# HOL-Nova.net
KiCad netlist of a schematic drawn in Altium Designer
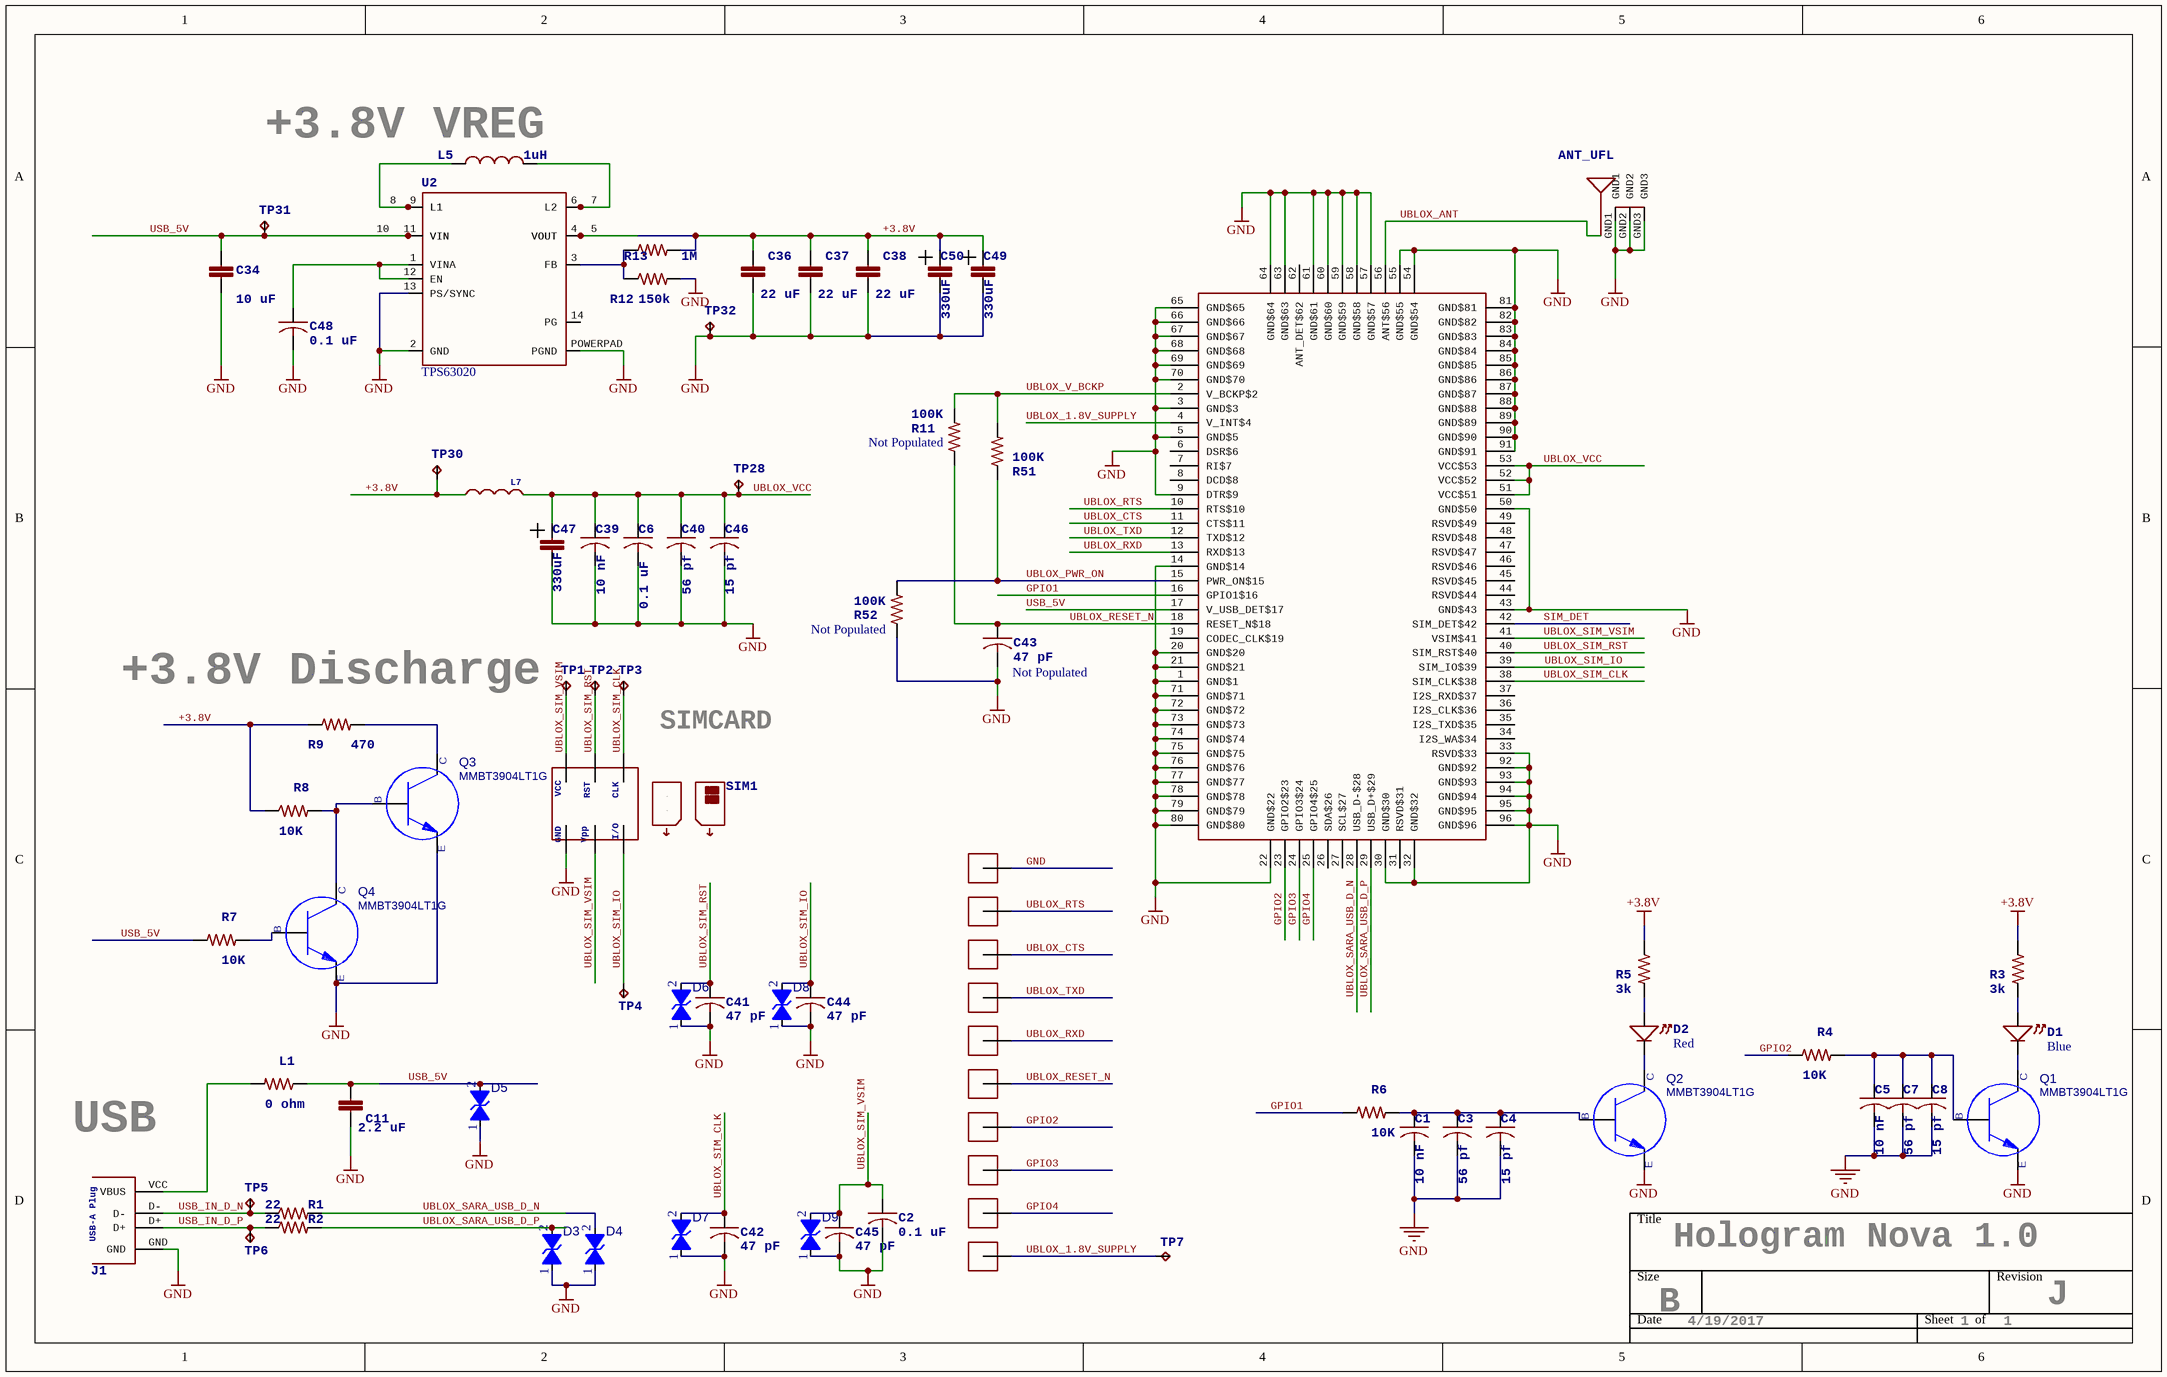
[diagram p0: HOL-Nova.SchDoc]

(export (version "E")
  (design (tool "Eeschema 10.0.6"))
  (components
    (comp (ref "ANT_UFL")
      (value "ANT-A-1JB")
      (footprint "UFL")
      (fields (field (name "MFG") "Amphenol") (field (name "MPN") "A-1JB"))
      (libsource (lib "KON-SU260") (part "ANT-A-1JB"))
    )
    (comp (ref "C1")
      (value "10 nF")
      (footprint "KON-SU260:CAP0402")
      (description "CAPACITOR, American symbol")
      (fields (field (name "MFG") "MURATA") (field (name "MPN") "GRM155R71C103KA01D"))
      (libsource (lib "KON-SU260") (part "CAP10nF_0402"))
    )
    (comp (ref "C2")
      (value "0.1 uF")
      (footprint "KON-SU260:CAP0402")
      (description "CAPACITOR, American symbol")
      (fields (field (name "MFG") "MURATA") (field (name "MPN") "GRM155R61C104KA88D"))
      (libsource (lib "KON-SU260") (part "CAP0.1uF_0402"))
    )
    (comp (ref "C3")
      (value "56 pf")
      (footprint "KON-SU260:CAP0402")
      (description "CAPACITOR, American symbol")
      (fields (field (name "MFG") "KEMET") (field (name "MPN") "C0402C560J5GACTU"))
      (libsource (lib "KON-SU260") (part "CAP56pF_0402"))
    )
    (comp (ref "C4")
      (value "15 pf")
      (footprint "KON-SU260:CAP0402")
      (description "CAPACITOR, American symbol")
      (fields (field (name "MFG") "AVX/ELCO") (field (name "MPN") "04025A150JAT2A"))
      (libsource (lib "KON-SU260") (part "CAP15pF_0402"))
    )
    (comp (ref "C5")
      (value "10 nF")
      (footprint "KON-SU260:CAP0402")
      (description "CAPACITOR, American symbol")
      (fields (field (name "MFG") "MURATA") (field (name "MPN") "GRM155R71C103KA01D"))
      (libsource (lib "KON-SU260") (part "CAP10nF_0402"))
    )
    (comp (ref "C6")
      (value "0.1 uF")
      (footprint "KON-SU260:CAP0402")
      (description "CAPACITOR, American symbol")
      (fields (field (name "MFG") "MURATA") (field (name "MPN") "GRM155R61C104KA88D"))
      (libsource (lib "KON-SU260") (part "CAP0.1uF_0402"))
    )
    (comp (ref "C7")
      (value "56 pf")
      (footprint "KON-SU260:CAP0402")
      (description "CAPACITOR, American symbol")
      (fields (field (name "MFG") "KEMET") (field (name "MPN") "C0402C560J5GACTU"))
      (libsource (lib "KON-SU260") (part "CAP56pF_0402"))
    )
    (comp (ref "C8")
      (value "15 pf")
      (footprint "KON-SU260:CAP0402")
      (description "CAPACITOR, American symbol")
      (fields (field (name "MFG") "AVX/ELCO") (field (name "MPN") "04025A150JAT2A"))
      (libsource (lib "KON-SU260") (part "CAP15pF_0402"))
    )
    (comp (ref "C11")
      (value "2.2 uF")
      (footprint "KON-SU260:CAP0603")
      (description "Ceramic Capacitor SMD")
      (fields (field (name "MPN") "CL10A225MQ8NNNC") (field (name "MFG") "SAMSUNG"))
      (libsource (lib "KON-SU260") (part "CAP2.2uF_0603"))
    )
    (comp (ref "C34")
      (value "10 uF")
      (footprint "KON-SU260:CAP0603")
      (description "Ceramic Capacitor SMD")
      (fields (field (name "MPN") "GRM188R60J106ME84D") (field (name "MFG") "Murata"))
      (libsource (lib "KON-SU260") (part "CAP10uF_0603"))
    )
    (comp (ref "C36")
      (value "22 uF")
      (footprint "KON-SU260:CAP0603")
      (description "Ceramic Capacitor SMD")
      (fields (field (name "MPN") "GRM188R60J226MEA0D") (field (name "MFG") "MURATA"))
      (libsource (lib "KON-SU260") (part "CAP22uF_0603"))
    )
    (comp (ref "C37")
      (value "22 uF")
      (footprint "KON-SU260:CAP0603")
      (description "Ceramic Capacitor SMD")
      (fields (field (name "MPN") "GRM188R60J226MEA0D") (field (name "MFG") "MURATA"))
      (libsource (lib "KON-SU260") (part "CAP22uF_0603"))
    )
    (comp (ref "C38")
      (value "22 uF")
      (footprint "KON-SU260:CAP0603")
      (description "Ceramic Capacitor SMD")
      (fields (field (name "MPN") "GRM188R60J226MEA0D") (field (name "MFG") "MURATA"))
      (libsource (lib "KON-SU260") (part "CAP22uF_0603"))
    )
    (comp (ref "C39")
      (value "10 nF")
      (footprint "KON-SU260:CAP0402")
      (description "CAPACITOR, American symbol")
      (fields (field (name "MFG") "MURATA") (field (name "MPN") "GRM155R71C103KA01D"))
      (libsource (lib "KON-SU260") (part "CAP10nF_0402"))
    )
    (comp (ref "C40")
      (value "56 pf")
      (footprint "KON-SU260:CAP0402")
      (description "CAPACITOR, American symbol")
      (fields (field (name "MFG") "KEMET") (field (name "MPN") "C0402C560J5GACTU"))
      (libsource (lib "KON-SU260") (part "CAP56pF_0402"))
    )
    (comp (ref "C41")
      (value "47 pF")
      (footprint "KON-SU260:CAP0402")
      (description "CAPACITOR, American symbol")
      (fields (field (name "MFG") "AVX") (field (name "MPN") "04025A470JAT2A"))
      (libsource (lib "KON-SU260") (part "CAP47pf_0402"))
    )
    (comp (ref "C42")
      (value "47 pF")
      (footprint "KON-SU260:CAP0402")
      (description "CAPACITOR, American symbol")
      (fields (field (name "MFG") "AVX") (field (name "MPN") "04025A470JAT2A"))
      (libsource (lib "KON-SU260") (part "CAP47pf_0402"))
    )
    (comp (ref "C43")
      (value "47 pF")
      (footprint "KON-SU260:CAP0402")
      (description "CAPACITOR, American symbol")
      (fields
        (field (name "MFG") "AVX")
        (field (name "MPN") "04025A470JAT2A")
        (field (name "NP") "Not Populated")
      )
      (libsource (lib "KON-SU260") (part "CAP47pf_0402"))
    )
    (comp (ref "C44")
      (value "47 pF")
      (footprint "KON-SU260:CAP0402")
      (description "CAPACITOR, American symbol")
      (fields (field (name "MFG") "AVX") (field (name "MPN") "04025A470JAT2A"))
      (libsource (lib "KON-SU260") (part "CAP47pf_0402"))
    )
    (comp (ref "C45")
      (value "47 pF")
      (footprint "KON-SU260:CAP0402")
      (description "CAPACITOR, American symbol")
      (fields (field (name "MFG") "AVX") (field (name "MPN") "04025A470JAT2A"))
      (libsource (lib "KON-SU260") (part "CAP47pf_0402"))
    )
    (comp (ref "C46")
      (value "15 pf")
      (footprint "KON-SU260:CAP0402")
      (description "CAPACITOR, American symbol")
      (fields (field (name "MFG") "AVX/ELCO") (field (name "MPN") "04025A150JAT2A"))
      (libsource (lib "KON-SU260") (part "CAP15pF_0402"))
    )
    (comp (ref "C47")
      (value "330uF")
      (footprint "KON-SU260:CAP1210POL")
      (description "Capacitor")
      (fields (field (name "MPN") "F950J337MBAAQ2") (field (name "MFG") "AVX"))
      (libsource (lib "KON-SU260") (part "CAP330uF_1210P"))
    )
    (comp (ref "C48")
      (value "0.1 uF")
      (footprint "KON-SU260:CAP0402")
      (description "CAPACITOR, American symbol")
      (fields (field (name "MFG") "MURATA") (field (name "MPN") "GRM155R61C104KA88D"))
      (libsource (lib "KON-SU260") (part "CAP0.1uF_0402"))
    )
    (comp (ref "C49")
      (value "330uF")
      (footprint "KON-SU260:CAP1210POL")
      (description "Capacitor")
      (fields (field (name "MPN") "F950J337MBAAQ2") (field (name "MFG") "AVX"))
      (libsource (lib "KON-SU260") (part "CAP330uF_1210P"))
    )
    (comp (ref "C50")
      (value "330uF")
      (footprint "KON-SU260:CAP1210POL")
      (description "Capacitor")
      (fields (field (name "MPN") "F950J337MBAAQ2") (field (name "MFG") "AVX"))
      (libsource (lib "KON-SU260") (part "CAP330uF_1210P"))
    )
    (comp (ref "D1")
      (value "LED_0402_VLMB")
      (footprint "LED_0402_VISHAY_VLMB")
      (description "LED, Vishay Blue 0402")
      (fields
        (field (name "MFG") "VISHAY")
        (field (name "MPN") "VLMB1500-GS08")
        (field (name "COLOR") "Blue")
      )
      (libsource (lib "KON-SU260") (part "LED_0402_VLMB"))
    )
    (comp (ref "D2")
      (value "LED_0402_VLMS")
      (footprint "LED_0402_VISHAY_VLMS")
      (description "LED, Vishay Red 0402")
      (fields (field (name "MFG") "VISHAY") (field (name "MPN") "VLMS1500-GS08") (field (name "COLOR") "Red"))
      (libsource (lib "KON-SU260") (part "LED_0402_VLMS"))
    )
    (comp (ref "D3")
      (value "~")
      (footprint "PESD_0402")
      (description "DIODE,ZENER VOLTAGE SUPPRESSOR,+/-14V")
      (fields (field (name "MFG") "Littlefuse") (field (name "MPN") "PESD0402-140"))
      (libsource (lib "KON-SU260") (part "PESD_14V"))
    )
    (comp (ref "D4")
      (value "~")
      (footprint "PESD_0402")
      (description "DIODE,ZENER VOLTAGE SUPPRESSOR,+/-14V")
      (fields (field (name "MFG") "Littlefuse") (field (name "MPN") "PESD0402-140"))
      (libsource (lib "KON-SU260") (part "PESD_14V"))
    )
    (comp (ref "D5")
      (value "~")
      (footprint "PESD_0402")
      (description "DIODE,ZENER VOLTAGE SUPPRESSOR,+/-14V")
      (fields (field (name "MFG") "Littlefuse") (field (name "MPN") "PESD0402-140"))
      (libsource (lib "KON-SU260") (part "PESD_14V"))
    )
    (comp (ref "D6")
      (value "~")
      (footprint "PESD_0402")
      (description "DIODE,ZENER VOLTAGE SUPPRESSOR,+/-14V")
      (fields (field (name "MFG") "Littlefuse") (field (name "MPN") "PESD0402-140"))
      (libsource (lib "KON-SU260") (part "PESD_14V"))
    )
    (comp (ref "D7")
      (value "~")
      (footprint "PESD_0402")
      (description "DIODE,ZENER VOLTAGE SUPPRESSOR,+/-14V")
      (fields (field (name "MFG") "Littlefuse") (field (name "MPN") "PESD0402-140"))
      (libsource (lib "KON-SU260") (part "PESD_14V"))
    )
    (comp (ref "D8")
      (value "~")
      (footprint "PESD_0402")
      (description "DIODE,ZENER VOLTAGE SUPPRESSOR,+/-14V")
      (fields (field (name "MFG") "Littlefuse") (field (name "MPN") "PESD0402-140"))
      (libsource (lib "KON-SU260") (part "PESD_14V"))
    )
    (comp (ref "D9")
      (value "~")
      (footprint "PESD_0402")
      (description "DIODE,ZENER VOLTAGE SUPPRESSOR,+/-14V")
      (fields (field (name "MFG") "Littlefuse") (field (name "MPN") "PESD0402-140"))
      (libsource (lib "KON-SU260") (part "PESD_14V"))
    )
    (comp (ref "J1")
      (value "USB_A_PLUG_MOLEX_0480372200")
      (footprint "USB_A_PLUG_MOLEX_0480372200 - clipped_copper")
      (description "Connector, USB A, Plug, 0480372200")
      (fields
        (field (name "MFG") "MOLEX")
        (field (name "MPN") "0480372200")
        (field (name "USB-A") "USB-A Plug")
      )
      (libsource (lib "KON-SU260") (part "USB_A_PLUG_MOLEX_0480372200"))
    )
    (comp (ref "L1")
      (value "0 ohm")
      (footprint "KON-SU260:RES0603")
      (description "Resistor, 0 ohm, 0603 case")
      (fields (field (name "MFG") "YAEGO") (field (name "MPN") "RC0603JR-070RL"))
      (libsource (lib "KON-SU260") (part "RES0R_0603"))
    )
    (comp (ref "L5")
      (value "1uH")
      (footprint "COILCRAFT_XFL4020")
      (fields (field (name "MPN") "XFL4020-102MEC") (field (name "MFG") "Coilcraft"))
      (libsource (lib "KON-SU260") (part "INDUCTOR_1UH_XFL4020-102MEC"))
    )
    (comp (ref "L7")
      (value "FerriteBead 120ohm, 3A")
      (footprint "KON-SU260:RES0603")
      (fields (field (name "MPN") "BLM18KG121TN1D") (field (name "MFG") "Murata"))
      (libsource (lib "KON-SU260") (part "FerriteBead_120ohm_3A"))
    )
    (comp (ref "Q1")
      (value "~")
      (footprint "SOT23")
      (description "TSTR,NPN 3904, SOT23")
      (fields (field (name "MFG") "ON Semiconductor") (field (name "MPN") "MMBT3904LT1G"))
      (libsource (lib "KON-SU260") (part "TSTR_3904_SOT23"))
    )
    (comp (ref "Q2")
      (value "~")
      (footprint "SOT23")
      (description "TSTR,NPN 3904, SOT23")
      (fields (field (name "MFG") "ON Semiconductor") (field (name "MPN") "MMBT3904LT1G"))
      (libsource (lib "KON-SU260") (part "TSTR_3904_SOT23"))
    )
    (comp (ref "Q3")
      (value "~")
      (footprint "SOT23")
      (description "TSTR,NPN 3904, SOT23")
      (fields (field (name "MFG") "ON Semiconductor") (field (name "MPN") "MMBT3904LT1G"))
      (libsource (lib "KON-SU260") (part "TSTR_3904_SOT23"))
    )
    (comp (ref "Q4")
      (value "~")
      (footprint "SOT23")
      (description "TSTR,NPN 3904, SOT23")
      (fields (field (name "MFG") "ON Semiconductor") (field (name "MPN") "MMBT3904LT1G"))
      (libsource (lib "KON-SU260") (part "TSTR_3904_SOT23"))
    )
    (comp (ref "R1")
      (value "22")
      (footprint "KON-SU260:RES0402")
      (description "Resistor, 22 ohm, 0402 case, 1%")
      (fields (field (name "MFG") "YAEGO") (field (name "MPN") "RC0402FR-0722RL"))
      (libsource (lib "KON-SU260") (part "RES22R_0402"))
    )
    (comp (ref "R2")
      (value "22")
      (footprint "KON-SU260:RES0402")
      (description "Resistor, 22 ohm, 0402 case, 1%")
      (fields (field (name "MFG") "YAEGO") (field (name "MPN") "RC0402FR-0722RL"))
      (libsource (lib "KON-SU260") (part "RES22R_0402"))
    )
    (comp (ref "R3")
      (value "3k")
      (footprint "KON-SU260:RES0402")
      (description "Resistor, 3K ohm, 0402 case, 1%")
      (fields (field (name "MFG") "YAEGO") (field (name "MPN") "RC0402FR-073KL"))
      (libsource (lib "KON-SU260") (part "RES3K_0402"))
    )
    (comp (ref "R4")
      (value "10K")
      (footprint "KON-SU260:RES0402")
      (description "Resistor, 10k ohm, 0402")
      (fields (field (name "MFG") "YAEGO") (field (name "MPN") "RC0402JR-0710KL"))
      (libsource (lib "KON-SU260") (part "RES10K_0402"))
    )
    (comp (ref "R5")
      (value "3k")
      (footprint "KON-SU260:RES0402")
      (description "Resistor, 3K ohm, 0402 case, 1%")
      (fields (field (name "MFG") "YAEGO") (field (name "MPN") "RC0402FR-073KL"))
      (libsource (lib "KON-SU260") (part "RES3K_0402"))
    )
    (comp (ref "R6")
      (value "10K")
      (footprint "KON-SU260:RES0402")
      (description "Resistor, 10k ohm, 0402")
      (fields (field (name "MFG") "YAEGO") (field (name "MPN") "RC0402JR-0710KL"))
      (libsource (lib "KON-SU260") (part "RES10K_0402"))
    )
    (comp (ref "R7")
      (value "10K")
      (footprint "KON-SU260:RES0402")
      (description "Resistor, 10k ohm, 0402")
      (fields (field (name "MFG") "YAEGO") (field (name "MPN") "RC0402JR-0710KL"))
      (libsource (lib "KON-SU260") (part "RES10K_0402"))
    )
    (comp (ref "R8")
      (value "10K")
      (footprint "KON-SU260:RES0402")
      (description "Resistor, 10k ohm, 0402")
      (fields (field (name "MFG") "YAEGO") (field (name "MPN") "RC0402JR-0710KL"))
      (libsource (lib "KON-SU260") (part "RES10K_0402"))
    )
    (comp (ref "R9")
      (value "470")
      (footprint "KON-SU260:RES0402")
      (description "Resistor, 470 ohm, 0402 case, 1%")
      (fields (field (name "MFG") "PANASONIC") (field (name "MPN") "ERJ-2GEJ471X"))
      (libsource (lib "KON-SU260") (part "RES470R_0402"))
    )
    (comp (ref "R11")
      (value "100K")
      (footprint "KON-SU260:RES0402")
      (description "Resistor, 100k ohm, 0402")
      (fields
        (field (name "MFG") "PANASONIC")
        (field (name "MPN") "ERJ-2GEJ104X")
        (field (name "NP") "Not Populated")
      )
      (libsource (lib "KON-SU260") (part "RES100K_0402"))
    )
    (comp (ref "R12")
      (value "150k")
      (footprint "KON-SU260:RES0402")
      (description "Res, 150k ohm, 0402 case, 1%")
      (fields (field (name "MFG") "YAEGO") (field (name "MPN") "RC0402FR-07150KL"))
      (libsource (lib "KON-SU260") (part "RES150K_0402"))
    )
    (comp (ref "R13")
      (value "1M")
      (footprint "KON-SU260:RES0402")
      (description "Resistor, 1M ohm, 0402 case, 1%")
      (fields (field (name "MFG") "YAEGO") (field (name "MPN") "RC0402FR-071ML"))
      (libsource (lib "KON-SU260") (part "RES1M_0402"))
    )
    (comp (ref "R51")
      (value "100K")
      (footprint "KON-SU260:RES0402")
      (description "Resistor, 100k ohm, 0402")
      (fields (field (name "MFG") "PANASONIC") (field (name "MPN") "ERJ-2GEJ104X"))
      (libsource (lib "KON-SU260") (part "RES100K_0402"))
    )
    (comp (ref "R52")
      (value "100K")
      (footprint "KON-SU260:RES0402")
      (description "Resistor, 100k ohm, 0402")
      (fields
        (field (name "MFG") "PANASONIC")
        (field (name "MPN") "ERJ-2GEJ104X")
        (field (name "NP") "Not Populated")
      )
      (libsource (lib "KON-SU260") (part "RES100K_0402"))
    )
    (comp (ref "SIM1")
      (value "SIM_CARD_NANO")
      (footprint "SIM_CARD_NANO")
      (fields
        (field (name "MFG") "GLOBAL CONNECTOR TECHNOLOGY")
        (field (name "MPN") "SIM8050-6-0-14-01-A")
        (field (name "VCC") "VCC")
        (field (name "RST") "RST")
        (field (name "CLK") "CLK")
        (field (name "I/O") "I/O")
        (field (name "VPP") "Vpp")
        (field (name "GND") "GND")
      )
      (libsource (lib "KON-SU260") (part "SIM_CARD_NANO"))
    )
    (comp (ref "T1") (value "TESTPAD") (footprint "TESTPAD") (libsource (lib "KON-SU260") (part "TESTPAD")))
    (comp (ref "T2") (value "TESTPAD") (footprint "TESTPAD") (libsource (lib "KON-SU260") (part "TESTPAD")))
    (comp (ref "T3") (value "TESTPAD") (footprint "TESTPAD") (libsource (lib "KON-SU260") (part "TESTPAD")))
    (comp (ref "T4") (value "TESTPAD") (footprint "TESTPAD") (libsource (lib "KON-SU260") (part "TESTPAD")))
    (comp (ref "T5") (value "TESTPAD") (footprint "TESTPAD") (libsource (lib "KON-SU260") (part "TESTPAD")))
    (comp (ref "T6") (value "TESTPAD") (footprint "TESTPAD") (libsource (lib "KON-SU260") (part "TESTPAD")))
    (comp (ref "T7") (value "TESTPAD") (footprint "TESTPAD") (libsource (lib "KON-SU260") (part "TESTPAD")))
    (comp (ref "T8") (value "TESTPAD") (footprint "TESTPAD") (libsource (lib "KON-SU260") (part "TESTPAD")))
    (comp (ref "T9") (value "TESTPAD") (footprint "TESTPAD") (libsource (lib "KON-SU260") (part "TESTPAD")))
    (comp (ref "T10") (value "TESTPAD") (footprint "TESTPAD") (libsource (lib "KON-SU260") (part "TESTPAD")))
    (comp (ref "TP1")
      (value "TPTP08R")
      (footprint "TP08R")
      (description "Test pad")
      (libsource (lib "KON-SU260") (part "TPTP08R"))
    )
    (comp (ref "TP2")
      (value "TPTP08R")
      (footprint "TP08R")
      (description "Test pad")
      (libsource (lib "KON-SU260") (part "TPTP08R"))
    )
    (comp (ref "TP3")
      (value "TPTP08R")
      (footprint "TP08R")
      (description "Test pad")
      (libsource (lib "KON-SU260") (part "TPTP08R"))
    )
    (comp (ref "TP4")
      (value "TPTP08R")
      (footprint "TP08R")
      (description "Test pad")
      (libsource (lib "KON-SU260") (part "TPTP08R"))
    )
    (comp (ref "TP5")
      (value "TPTP08R")
      (footprint "TP08R")
      (description "Test pad")
      (libsource (lib "KON-SU260") (part "TPTP08R"))
    )
    (comp (ref "TP6")
      (value "TPTP08R")
      (footprint "TP08R")
      (description "Test pad")
      (libsource (lib "KON-SU260") (part "TPTP08R"))
    )
    (comp (ref "TP7")
      (value "TPTP08R")
      (footprint "TP08R")
      (description "Test pad")
      (libsource (lib "KON-SU260") (part "TPTP08R"))
    )
    (comp (ref "TP28")
      (value "TPTP08R")
      (footprint "TP08R")
      (description "Test pad")
      (libsource (lib "KON-SU260") (part "TPTP08R"))
    )
    (comp (ref "TP30")
      (value "TPTP08R")
      (footprint "TP08R")
      (description "Test pad")
      (libsource (lib "KON-SU260") (part "TPTP08R"))
    )
    (comp (ref "TP31")
      (value "TPTP08R")
      (footprint "TP08R")
      (description "Test pad")
      (libsource (lib "KON-SU260") (part "TPTP08R"))
    )
    (comp (ref "TP32")
      (value "TPTP08R")
      (footprint "TP08R")
      (description "Test pad")
      (libsource (lib "KON-SU260") (part "TPTP08R"))
    )
    (comp (ref "U2")
      (value "TPS63020")
      (footprint "QFN-14-POWERPAD3X4DSJ")
      (description "Regulator, Boost Buck, 3A")
      (fields (field (name "MFG") "TI") (field (name "MPN") "TPS63020DSJ"))
      (libsource (lib "KON-SU260") (part "TPS63020"))
    )
    (comp (ref "U16")
      (value "SARA-U2XX")
      (footprint "KON-SU260:SARA")
      (fields (field (name "MFG") "U-BLOX") (field (name "MPN") "SARA-U260-00S"))
      (libsource (lib "KON-SU260") (part "SARA-U2XX"))
    )
  )
  (nets
    (net (code "1") (name "+3.8V") (class "Default")
      (node (ref "C36") (pin "1") (pinfunction "1_1") (pintype "passive"))
      (node (ref "C37") (pin "1") (pinfunction "1_1") (pintype "passive"))
      (node (ref "C38") (pin "1") (pinfunction "1_1") (pintype "passive"))
      (node (ref "C49") (pin "1") (pinfunction "1_1") (pintype "passive"))
      (node (ref "C50") (pin "1") (pinfunction "1_1") (pintype "passive"))
      (node (ref "L7") (pin "2") (pinfunction "P$2_2") (pintype "passive"))
      (node (ref "R13") (pin "2") (pinfunction "2_2") (pintype "passive"))
      (node (ref "R3") (pin "1") (pinfunction "1_1") (pintype "passive"))
      (node (ref "R5") (pin "1") (pinfunction "1_1") (pintype "passive"))
      (node (ref "R8") (pin "1") (pinfunction "1_1") (pintype "passive"))
      (node (ref "R9") (pin "1") (pinfunction "1_1") (pintype "passive"))
      (node (ref "TP30") (pin "TP") (pinfunction "TP_TP") (pintype "passive"))
      (node (ref "U2") (pin "4") (pinfunction "VOUT_4") (pintype "passive"))
      (node (ref "U2") (pin "5") (pinfunction "VOUT_5") (pintype "passive"))
    )
    (net (code "2") (name "/GPIO1") (class "Default")
      (node (ref "R6") (pin "1") (pinfunction "1_1") (pintype "passive"))
      (node (ref "U16") (pin "16") (pinfunction "GPIO1$16_16") (pintype "passive"))
    )
    (net (code "3") (name "/GPIO2") (class "Default")
      (node (ref "R4") (pin "1") (pinfunction "1_1") (pintype "passive"))
      (node (ref "T6") (pin "P$1") (pinfunction "P$1_P$1") (pintype "passive"))
      (node (ref "U16") (pin "23") (pinfunction "GPIO2$23_23") (pintype "power_in"))
    )
    (net (code "4") (name "/GPIO3") (class "Default")
      (node (ref "T7") (pin "P$1") (pinfunction "P$1_P$1") (pintype "passive"))
      (node (ref "U16") (pin "24") (pinfunction "GPIO3$24_24") (pintype "passive"))
    )
    (net (code "5") (name "/GPIO4") (class "Default")
      (node (ref "T8") (pin "P$1") (pinfunction "P$1_P$1") (pintype "passive"))
      (node (ref "U16") (pin "25") (pinfunction "GPIO4$25_25") (pintype "power_in"))
    )
    (net (code "6") (name "/SIM_DET") (class "Default")
      (node (ref "U16") (pin "42") (pinfunction "SIM_DET$42_42") (pintype "passive"))
    )
    (net (code "7") (name "/UBLOX_1.8V_SUPPLY") (class "Default")
      (node (ref "T9") (pin "P$1") (pinfunction "P$1_P$1") (pintype "passive"))
      (node (ref "TP7") (pin "TP") (pinfunction "TP_TP") (pintype "passive"))
      (node (ref "U16") (pin "4") (pinfunction "V_INT$4_4") (pintype "passive"))
    )
    (net (code "8") (name "/UBLOX_ANT") (class "Default")
      (node (ref "ANT_UFL") (pin "SIGNAL") (pinfunction "SIGNAL_SIGNAL") (pintype "passive"))
      (node (ref "U16") (pin "56") (pinfunction "ANT$56_56") (pintype "power_in"))
    )
    (net (code "9") (name "/UBLOX_CTS") (class "Default")
      (node (ref "T2") (pin "P$1") (pinfunction "P$1_P$1") (pintype "passive"))
      (node (ref "U16") (pin "11") (pinfunction "CTS$11_11") (pintype "passive"))
    )
    (net (code "10") (name "/UBLOX_PWR_ON") (class "Default")
      (node (ref "R51") (pin "1") (pinfunction "1_1") (pintype "passive"))
      (node (ref "R52") (pin "2") (pinfunction "2_2") (pintype "passive"))
      (node (ref "U16") (pin "15") (pinfunction "PWR_ON$15_15") (pintype "passive"))
    )
    (net (code "11") (name "/UBLOX_RESET_N") (class "Default")
      (node (ref "C43") (pin "1") (pinfunction "1_1") (pintype "passive"))
      (node (ref "R11") (pin "1") (pinfunction "1_1") (pintype "passive"))
      (node (ref "T5") (pin "P$1") (pinfunction "P$1_P$1") (pintype "passive"))
      (node (ref "U16") (pin "18") (pinfunction "RESET_N$18_18") (pintype "passive"))
    )
    (net (code "12") (name "/UBLOX_RTS") (class "Default")
      (node (ref "T1") (pin "P$1") (pinfunction "P$1_P$1") (pintype "passive"))
      (node (ref "U16") (pin "10") (pinfunction "RTS$10_10") (pintype "passive"))
    )
    (net (code "13") (name "/UBLOX_RXD") (class "Default")
      (node (ref "T4") (pin "P$1") (pinfunction "P$1_P$1") (pintype "passive"))
      (node (ref "U16") (pin "13") (pinfunction "RXD$13_13") (pintype "passive"))
    )
    (net (code "14") (name "/UBLOX_SARA_USB_D_N") (class "Default")
      (node (ref "D4") (pin "2") (pinfunction "2_2") (pintype "passive"))
      (node (ref "R1") (pin "2") (pinfunction "2_2") (pintype "passive"))
      (node (ref "U16") (pin "28") (pinfunction "USB_D-$28_28") (pintype "power_in"))
    )
    (net (code "15") (name "/UBLOX_SARA_USB_D_P") (class "Default")
      (node (ref "D3") (pin "2") (pinfunction "2_2") (pintype "passive"))
      (node (ref "R2") (pin "2") (pinfunction "2_2") (pintype "passive"))
      (node (ref "U16") (pin "29") (pinfunction "USB_D+$29_29") (pintype "power_in"))
    )
    (net (code "16") (name "/UBLOX_SIM_CLK") (class "Default")
      (node (ref "C42") (pin "1") (pinfunction "1_1") (pintype "passive"))
      (node (ref "D7") (pin "2") (pinfunction "2_2") (pintype "passive"))
      (node (ref "SIM1") (pin "C3") (pinfunction "CLK_C3") (pintype "passive"))
      (node (ref "TP3") (pin "TP") (pinfunction "TP_TP") (pintype "passive"))
      (node (ref "U16") (pin "38") (pinfunction "SIM_CLK$38_38") (pintype "power_in"))
    )
    (net (code "17") (name "/UBLOX_SIM_IO") (class "Default")
      (node (ref "C44") (pin "1") (pinfunction "1_1") (pintype "passive"))
      (node (ref "D8") (pin "2") (pinfunction "2_2") (pintype "passive"))
      (node (ref "SIM1") (pin "C7") (pinfunction "IO_C7") (pintype "passive"))
      (node (ref "TP4") (pin "TP") (pinfunction "TP_TP") (pintype "passive"))
      (node (ref "U16") (pin "39") (pinfunction "SIM_IO$39_39") (pintype "power_in"))
    )
    (net (code "18") (name "/UBLOX_SIM_RST") (class "Default")
      (node (ref "C41") (pin "1") (pinfunction "1_1") (pintype "passive"))
      (node (ref "D6") (pin "2") (pinfunction "2_2") (pintype "passive"))
      (node (ref "SIM1") (pin "C2") (pinfunction "RST_C2") (pintype "passive"))
      (node (ref "TP2") (pin "TP") (pinfunction "TP_TP") (pintype "passive"))
      (node (ref "U16") (pin "40") (pinfunction "SIM_RST$40_40") (pintype "power_in"))
    )
    (net (code "19") (name "/UBLOX_SIM_VSIM") (class "Default")
      (node (ref "C2") (pin "1") (pinfunction "1_1") (pintype "passive"))
      (node (ref "C45") (pin "1") (pinfunction "1_1") (pintype "passive"))
      (node (ref "D9") (pin "2") (pinfunction "2_2") (pintype "passive"))
      (node (ref "SIM1") (pin "C1") (pinfunction "VCC_C1") (pintype "passive"))
      (node (ref "SIM1") (pin "C6") (pinfunction "VCC2_C6") (pintype "passive"))
      (node (ref "TP1") (pin "TP") (pinfunction "TP_TP") (pintype "passive"))
      (node (ref "U16") (pin "41") (pinfunction "VSIM$41_41") (pintype "passive"))
    )
    (net (code "20") (name "/UBLOX_TXD") (class "Default")
      (node (ref "T3") (pin "P$1") (pinfunction "P$1_P$1") (pintype "passive"))
      (node (ref "U16") (pin "12") (pinfunction "TXD$12_12") (pintype "power_in"))
    )
    (net (code "21") (name "/UBLOX_VCC") (class "Default")
      (node (ref "C39") (pin "1") (pinfunction "1_1") (pintype "passive"))
      (node (ref "C40") (pin "1") (pinfunction "1_1") (pintype "passive"))
      (node (ref "C46") (pin "1") (pinfunction "1_1") (pintype "passive"))
      (node (ref "C47") (pin "1") (pinfunction "1_1") (pintype "passive"))
      (node (ref "C6") (pin "1") (pinfunction "1_1") (pintype "passive"))
      (node (ref "L7") (pin "1") (pinfunction "P$1_1") (pintype "passive"))
      (node (ref "TP28") (pin "TP") (pinfunction "TP_TP") (pintype "passive"))
      (node (ref "U16") (pin "51") (pinfunction "VCC$51_51") (pintype "passive"))
      (node (ref "U16") (pin "52") (pinfunction "VCC$52_52") (pintype "passive"))
      (node (ref "U16") (pin "53") (pinfunction "VCC$53_53") (pintype "passive"))
    )
    (net (code "22") (name "/UBLOX_V_BCKP") (class "Default")
      (node (ref "R11") (pin "2") (pinfunction "2_2") (pintype "passive"))
      (node (ref "R51") (pin "2") (pinfunction "2_2") (pintype "passive"))
      (node (ref "U16") (pin "2") (pinfunction "V_BCKP$2_2") (pintype "passive"))
    )
    (net (code "23") (name "/USB_5V") (class "Default")
      (node (ref "C11") (pin "1") (pinfunction "1_1") (pintype "passive"))
      (node (ref "C34") (pin "1") (pinfunction "1_1") (pintype "passive"))
      (node (ref "D5") (pin "2") (pinfunction "2_2") (pintype "passive"))
      (node (ref "L1") (pin "1") (pinfunction "1_1") (pintype "passive"))
      (node (ref "R7") (pin "1") (pinfunction "1_1") (pintype "passive"))
      (node (ref "TP31") (pin "TP") (pinfunction "TP_TP") (pintype "passive"))
      (node (ref "U16") (pin "17") (pinfunction "V_USB_DET$17_17") (pintype "passive"))
      (node (ref "U2") (pin "10") (pinfunction "VIN_10") (pintype "passive"))
      (node (ref "U2") (pin "11") (pinfunction "VIN_11") (pintype "passive"))
    )
    (net (code "24") (name "/USB_IN_D_N") (class "Default")
      (node (ref "J1") (pin "D-") (pinfunction "D-_D-") (pintype "passive"))
      (node (ref "R1") (pin "1") (pinfunction "1_1") (pintype "passive"))
      (node (ref "TP5") (pin "TP") (pinfunction "TP_TP") (pintype "passive"))
    )
    (net (code "25") (name "/USB_IN_D_P") (class "Default")
      (node (ref "J1") (pin "D+") (pinfunction "D+_D+") (pintype "passive"))
      (node (ref "R2") (pin "1") (pinfunction "1_1") (pintype "passive"))
      (node (ref "TP6") (pin "TP") (pinfunction "TP_TP") (pintype "passive"))
    )
    (net (code "26") (name "GND") (class "Default")
      (node (ref "ANT_UFL") (pin "GND1") (pinfunction "GND1_GND1") (pintype "passive"))
      (node (ref "ANT_UFL") (pin "GND2") (pinfunction "GND2_GND2") (pintype "passive"))
      (node (ref "ANT_UFL") (pin "GND3") (pinfunction "GND3_GND3") (pintype "passive"))
      (node (ref "C1") (pin "2") (pinfunction "2_2") (pintype "passive"))
      (node (ref "C11") (pin "2") (pinfunction "2_2") (pintype "passive"))
      (node (ref "C2") (pin "2") (pinfunction "2_2") (pintype "passive"))
      (node (ref "C3") (pin "2") (pinfunction "2_2") (pintype "passive"))
      (node (ref "C34") (pin "2") (pinfunction "2_2") (pintype "passive"))
      (node (ref "C36") (pin "2") (pinfunction "2_2") (pintype "passive"))
      (node (ref "C37") (pin "2") (pinfunction "2_2") (pintype "passive"))
      (node (ref "C38") (pin "2") (pinfunction "2_2") (pintype "passive"))
      (node (ref "C39") (pin "2") (pinfunction "2_2") (pintype "passive"))
      (node (ref "C4") (pin "2") (pinfunction "2_2") (pintype "passive"))
      (node (ref "C40") (pin "2") (pinfunction "2_2") (pintype "passive"))
      (node (ref "C41") (pin "2") (pinfunction "2_2") (pintype "passive"))
      (node (ref "C42") (pin "2") (pinfunction "2_2") (pintype "passive"))
      (node (ref "C43") (pin "2") (pinfunction "2_2") (pintype "passive"))
      (node (ref "C44") (pin "2") (pinfunction "2_2") (pintype "passive"))
      (node (ref "C45") (pin "2") (pinfunction "2_2") (pintype "passive"))
      (node (ref "C46") (pin "2") (pinfunction "2_2") (pintype "passive"))
      (node (ref "C47") (pin "2") (pinfunction "2_2") (pintype "passive"))
      (node (ref "C48") (pin "2") (pinfunction "2_2") (pintype "passive"))
      (node (ref "C49") (pin "2") (pinfunction "2_2") (pintype "passive"))
      (node (ref "C5") (pin "2") (pinfunction "2_2") (pintype "passive"))
      (node (ref "C50") (pin "2") (pinfunction "2_2") (pintype "passive"))
      (node (ref "C6") (pin "2") (pinfunction "2_2") (pintype "passive"))
      (node (ref "C7") (pin "2") (pinfunction "2_2") (pintype "passive"))
      (node (ref "C8") (pin "2") (pinfunction "2_2") (pintype "passive"))
      (node (ref "D3") (pin "1") (pinfunction "1_1") (pintype "passive"))
      (node (ref "D4") (pin "1") (pinfunction "1_1") (pintype "passive"))
      (node (ref "D5") (pin "1") (pinfunction "1_1") (pintype "passive"))
      (node (ref "D6") (pin "1") (pinfunction "1_1") (pintype "passive"))
      (node (ref "D7") (pin "1") (pinfunction "1_1") (pintype "passive"))
      (node (ref "D8") (pin "1") (pinfunction "1_1") (pintype "passive"))
      (node (ref "D9") (pin "1") (pinfunction "1_1") (pintype "passive"))
      (node (ref "J1") (pin "GND") (pinfunction "GND_GND") (pintype "passive"))
      (node (ref "Q1") (pin "2") (pinfunction "E_2") (pintype "passive"))
      (node (ref "Q2") (pin "2") (pinfunction "E_2") (pintype "passive"))
      (node (ref "Q3") (pin "2") (pinfunction "E_2") (pintype "passive"))
      (node (ref "Q4") (pin "2") (pinfunction "E_2") (pintype "passive"))
      (node (ref "R12") (pin "2") (pinfunction "2_2") (pintype "passive"))
      (node (ref "R52") (pin "1") (pinfunction "1_1") (pintype "passive"))
      (node (ref "SIM1") (pin "C5") (pinfunction "GND_C5") (pintype "passive"))
      (node (ref "T10") (pin "P$1") (pinfunction "P$1_P$1") (pintype "passive"))
      (node (ref "TP32") (pin "TP") (pinfunction "TP_TP") (pintype "passive"))
      (node (ref "U16") (pin "1") (pinfunction "GND$1_1") (pintype "passive"))
      (node (ref "U16") (pin "14") (pinfunction "GND$14_14") (pintype "passive"))
      (node (ref "U16") (pin "20") (pinfunction "GND$20_20") (pintype "passive"))
      (node (ref "U16") (pin "21") (pinfunction "GND$21_21") (pintype "passive"))
      (node (ref "U16") (pin "22") (pinfunction "GND$22_22") (pintype "power_in"))
      (node (ref "U16") (pin "3") (pinfunction "GND$3_3") (pintype "passive"))
      (node (ref "U16") (pin "30") (pinfunction "GND$30_30") (pintype "passive"))
      (node (ref "U16") (pin "32") (pinfunction "GND$32_32") (pintype "power_in"))
      (node (ref "U16") (pin "33") (pinfunction "RSVD$33_33") (pintype "power_in"))
      (node (ref "U16") (pin "43") (pinfunction "GND$43_43") (pintype "passive"))
      (node (ref "U16") (pin "5") (pinfunction "GND$5_5") (pintype "passive"))
      (node (ref "U16") (pin "50") (pinfunction "GND$50_50") (pintype "passive"))
      (node (ref "U16") (pin "54") (pinfunction "GND$54_54") (pintype "power_in"))
      (node (ref "U16") (pin "55") (pinfunction "GND$55_55") (pintype "power_in"))
      (node (ref "U16") (pin "57") (pinfunction "GND$57_57") (pintype "power_in"))
      (node (ref "U16") (pin "58") (pinfunction "GND$58_58") (pintype "power_in"))
      (node (ref "U16") (pin "59") (pinfunction "GND$59_59") (pintype "power_in"))
      (node (ref "U16") (pin "60") (pinfunction "GND$60_60") (pintype "power_in"))
      (node (ref "U16") (pin "61") (pinfunction "GND$61_61") (pintype "power_in"))
      (node (ref "U16") (pin "63") (pinfunction "GND$63_63") (pintype "power_in"))
      (node (ref "U16") (pin "64") (pinfunction "GND$64_64") (pintype "power_in"))
      (node (ref "U16") (pin "65") (pinfunction "GND$65_65") (pintype "passive"))
      (node (ref "U16") (pin "66") (pinfunction "GND$66_66") (pintype "passive"))
      (node (ref "U16") (pin "67") (pinfunction "GND$67_67") (pintype "passive"))
      (node (ref "U16") (pin "68") (pinfunction "GND$68_68") (pintype "passive"))
      (node (ref "U16") (pin "69") (pinfunction "GND$69_69") (pintype "passive"))
      (node (ref "U16") (pin "70") (pinfunction "GND$70_70") (pintype "passive"))
      (node (ref "U16") (pin "71") (pinfunction "GND$71_71") (pintype "passive"))
      (node (ref "U16") (pin "72") (pinfunction "GND$72_72") (pintype "passive"))
      (node (ref "U16") (pin "73") (pinfunction "GND$73_73") (pintype "passive"))
      (node (ref "U16") (pin "74") (pinfunction "GND$74_74") (pintype "passive"))
      (node (ref "U16") (pin "75") (pinfunction "GND$75_75") (pintype "passive"))
      (node (ref "U16") (pin "76") (pinfunction "GND$76_76") (pintype "passive"))
      (node (ref "U16") (pin "77") (pinfunction "GND$77_77") (pintype "passive"))
      (node (ref "U16") (pin "78") (pinfunction "GND$78_78") (pintype "passive"))
      (node (ref "U16") (pin "79") (pinfunction "GND$79_79") (pintype "passive"))
      (node (ref "U16") (pin "80") (pinfunction "GND$80_80") (pintype "passive"))
      (node (ref "U16") (pin "81") (pinfunction "GND$81_81") (pintype "passive"))
      (node (ref "U16") (pin "82") (pinfunction "GND$82_82") (pintype "passive"))
      (node (ref "U16") (pin "83") (pinfunction "GND$83_83") (pintype "passive"))
      (node (ref "U16") (pin "84") (pinfunction "GND$84_84") (pintype "passive"))
      (node (ref "U16") (pin "85") (pinfunction "GND$85_85") (pintype "passive"))
      (node (ref "U16") (pin "86") (pinfunction "GND$86_86") (pintype "passive"))
      (node (ref "U16") (pin "87") (pinfunction "GND$87_87") (pintype "passive"))
      (node (ref "U16") (pin "88") (pinfunction "GND$88_88") (pintype "passive"))
      (node (ref "U16") (pin "89") (pinfunction "GND$89_89") (pintype "passive"))
      (node (ref "U16") (pin "9") (pinfunction "DTR$9_9") (pintype "passive"))
      (node (ref "U16") (pin "90") (pinfunction "GND$90_90") (pintype "passive"))
      (node (ref "U16") (pin "91") (pinfunction "GND$91_91") (pintype "passive"))
      (node (ref "U16") (pin "92") (pinfunction "GND$92_92") (pintype "passive"))
      (node (ref "U16") (pin "93") (pinfunction "GND$93_93") (pintype "passive"))
      (node (ref "U16") (pin "94") (pinfunction "GND$94_94") (pintype "passive"))
      (node (ref "U16") (pin "95") (pinfunction "GND$95_95") (pintype "passive"))
      (node (ref "U16") (pin "96") (pinfunction "GND$96_96") (pintype "passive"))
      (node (ref "U2") (pin "13") (pinfunction "PS/SYNC_13") (pintype "passive"))
      (node (ref "U2") (pin "2") (pinfunction "GND_2") (pintype "passive"))
      (node (ref "U2") (pin "POWERPAD") (pinfunction "PGND_POWERPAD") (pintype "passive"))
    )
    (net (code "27") (name "Net-(D1-PadANODE)") (class "Default")
      (node (ref "D1") (pin "ANODE") (pinfunction "ANODE_ANODE") (pintype "passive"))
      (node (ref "R3") (pin "2") (pinfunction "2_2") (pintype "passive"))
    )
    (net (code "28") (name "Net-(D2-PadANODE)") (class "Default")
      (node (ref "D2") (pin "ANODE") (pinfunction "ANODE_ANODE") (pintype "passive"))
      (node (ref "R5") (pin "2") (pinfunction "2_2") (pintype "passive"))
    )
    (net (code "29") (name "Net-(J1-VBUS)") (class "Default")
      (node (ref "J1") (pin "VCC") (pinfunction "VBUS_VCC") (pintype "passive"))
      (node (ref "L1") (pin "2") (pinfunction "2_2") (pintype "passive"))
    )
    (net (code "30") (name "Net-(L5-PadP$1)") (class "Default")
      (node (ref "L5") (pin "P$1") (pinfunction "P$1_P$1") (pintype "passive"))
      (node (ref "U2") (pin "8") (pinfunction "L1_8") (pintype "passive"))
      (node (ref "U2") (pin "9") (pinfunction "L1_9") (pintype "passive"))
    )
    (net (code "31") (name "Net-(L5-PadP$2)") (class "Default")
      (node (ref "L5") (pin "P$2") (pinfunction "P$2_P$2") (pintype "passive"))
      (node (ref "U2") (pin "6") (pinfunction "L2_6") (pintype "passive"))
      (node (ref "U2") (pin "7") (pinfunction "L2_7") (pintype "passive"))
    )
    (net (code "32") (name "Net-(Q1-B)") (class "Default")
      (node (ref "C5") (pin "1") (pinfunction "1_1") (pintype "passive"))
      (node (ref "C7") (pin "1") (pinfunction "1_1") (pintype "passive"))
      (node (ref "C8") (pin "1") (pinfunction "1_1") (pintype "passive"))
      (node (ref "Q1") (pin "1") (pinfunction "B_1") (pintype "passive"))
      (node (ref "R4") (pin "2") (pinfunction "2_2") (pintype "passive"))
    )
    (net (code "33") (name "Net-(Q1-C)") (class "Default")
      (node (ref "D1") (pin "CATHODE") (pinfunction "CATHODE_CATHODE") (pintype "passive"))
      (node (ref "Q1") (pin "3") (pinfunction "C_3") (pintype "passive"))
    )
    (net (code "34") (name "Net-(Q2-B)") (class "Default")
      (node (ref "C1") (pin "1") (pinfunction "1_1") (pintype "passive"))
      (node (ref "C3") (pin "1") (pinfunction "1_1") (pintype "passive"))
      (node (ref "C4") (pin "1") (pinfunction "1_1") (pintype "passive"))
      (node (ref "Q2") (pin "1") (pinfunction "B_1") (pintype "passive"))
      (node (ref "R6") (pin "2") (pinfunction "2_2") (pintype "passive"))
    )
    (net (code "35") (name "Net-(Q2-C)") (class "Default")
      (node (ref "D2") (pin "CATHODE") (pinfunction "CATHODE_CATHODE") (pintype "passive"))
      (node (ref "Q2") (pin "3") (pinfunction "C_3") (pintype "passive"))
    )
    (net (code "36") (name "Net-(Q3-B)") (class "Default")
      (node (ref "Q3") (pin "1") (pinfunction "B_1") (pintype "passive"))
      (node (ref "Q4") (pin "3") (pinfunction "C_3") (pintype "passive"))
      (node (ref "R8") (pin "2") (pinfunction "2_2") (pintype "passive"))
    )
    (net (code "37") (name "Net-(Q3-C)") (class "Default")
      (node (ref "Q3") (pin "3") (pinfunction "C_3") (pintype "passive"))
      (node (ref "R9") (pin "2") (pinfunction "2_2") (pintype "passive"))
    )
    (net (code "38") (name "Net-(Q4-B)") (class "Default")
      (node (ref "Q4") (pin "1") (pinfunction "B_1") (pintype "passive"))
      (node (ref "R7") (pin "2") (pinfunction "2_2") (pintype "passive"))
    )
    (net (code "39") (name "Net-(U2-EN)") (class "Default")
      (node (ref "C48") (pin "1") (pinfunction "1_1") (pintype "passive"))
      (node (ref "U2") (pin "1") (pinfunction "VINA_1") (pintype "passive"))
      (node (ref "U2") (pin "12") (pinfunction "EN_12") (pintype "passive"))
    )
    (net (code "40") (name "Net-(U2-FB)") (class "Default")
      (node (ref "R12") (pin "1") (pinfunction "1_1") (pintype "passive"))
      (node (ref "R13") (pin "1") (pinfunction "1_1") (pintype "passive"))
      (node (ref "U2") (pin "3") (pinfunction "FB_3") (pintype "passive"))
    )
    (net (code "41") (name "unconnected-(SIM1-NC1-PadMTG1)") (class "Default")
      (node (ref "SIM1") (pin "MTG1") (pinfunction "NC1_MTG1") (pintype "passive"))
    )
    (net (code "42") (name "unconnected-(SIM1-NC2-PadMTG2)") (class "Default")
      (node (ref "SIM1") (pin "MTG2") (pinfunction "NC2_MTG2") (pintype "passive"))
    )
    (net (code "43") (name "unconnected-(U2-PG-Pad14)") (class "Default")
      (node (ref "U2") (pin "14") (pinfunction "PG_14") (pintype "passive"))
    )
    (net (code "44") (name "unconnected-(U16-ANT_DET$62-Pad62)") (class "Default")
      (node (ref "U16") (pin "62") (pinfunction "ANT_DET$62_62") (pintype "power_in"))
    )
    (net (code "45") (name "unconnected-(U16-CODEC_CLK$19-Pad19)") (class "Default")
      (node (ref "U16") (pin "19") (pinfunction "CODEC_CLK$19_19") (pintype "passive"))
    )
    (net (code "46") (name "unconnected-(U16-DCD$8-Pad8)") (class "Default")
      (node (ref "U16") (pin "8") (pinfunction "DCD$8_8") (pintype "passive"))
    )
    (net (code "47") (name "unconnected-(U16-DSR$6-Pad6)") (class "Default")
      (node (ref "U16") (pin "6") (pinfunction "DSR$6_6") (pintype "passive"))
    )
    (net (code "48") (name "unconnected-(U16-I2S_CLK$36-Pad36)") (class "Default")
      (node (ref "U16") (pin "36") (pinfunction "I2S_CLK$36_36") (pintype "passive"))
    )
    (net (code "49") (name "unconnected-(U16-I2S_RXD$37-Pad37)") (class "Default")
      (node (ref "U16") (pin "37") (pinfunction "I2S_RXD$37_37") (pintype "passive"))
    )
    (net (code "50") (name "unconnected-(U16-I2S_TXD$35-Pad35)") (class "Default")
      (node (ref "U16") (pin "35") (pinfunction "I2S_TXD$35_35") (pintype "power_in"))
    )
    (net (code "51") (name "unconnected-(U16-I2S_WA$34-Pad34)") (class "Default")
      (node (ref "U16") (pin "34") (pinfunction "I2S_WA$34_34") (pintype "power_in"))
    )
    (net (code "52") (name "unconnected-(U16-RI$7-Pad7)") (class "Default")
      (node (ref "U16") (pin "7") (pinfunction "RI$7_7") (pintype "passive"))
    )
    (net (code "53") (name "unconnected-(U16-RSVD$31-Pad31)") (class "Default")
      (node (ref "U16") (pin "31") (pinfunction "RSVD$31_31") (pintype "power_in"))
    )
    (net (code "54") (name "unconnected-(U16-RSVD$44-Pad44)") (class "Default")
      (node (ref "U16") (pin "44") (pinfunction "RSVD$44_44") (pintype "passive"))
    )
    (net (code "55") (name "unconnected-(U16-RSVD$45-Pad45)") (class "Default")
      (node (ref "U16") (pin "45") (pinfunction "RSVD$45_45") (pintype "passive"))
    )
    (net (code "56") (name "unconnected-(U16-RSVD$46-Pad46)") (class "Default")
      (node (ref "U16") (pin "46") (pinfunction "RSVD$46_46") (pintype "passive"))
    )
    (net (code "57") (name "unconnected-(U16-RSVD$47-Pad47)") (class "Default")
      (node (ref "U16") (pin "47") (pinfunction "RSVD$47_47") (pintype "passive"))
    )
    (net (code "58") (name "unconnected-(U16-RSVD$48-Pad48)") (class "Default")
      (node (ref "U16") (pin "48") (pinfunction "RSVD$48_48") (pintype "passive"))
    )
    (net (code "59") (name "unconnected-(U16-RSVD$49-Pad49)") (class "Default")
      (node (ref "U16") (pin "49") (pinfunction "RSVD$49_49") (pintype "passive"))
    )
    (net (code "60") (name "unconnected-(U16-SCL$27-Pad27)") (class "Default")
      (node (ref "U16") (pin "27") (pinfunction "SCL$27_27") (pintype "power_in"))
    )
    (net (code "61") (name "unconnected-(U16-SDA$26-Pad26)") (class "Default")
      (node (ref "U16") (pin "26") (pinfunction "SDA$26_26") (pintype "power_in"))
    )
  )
)
